# LED-RingCoder.net
KiCad netlist of a schematic drawn in EAGLE
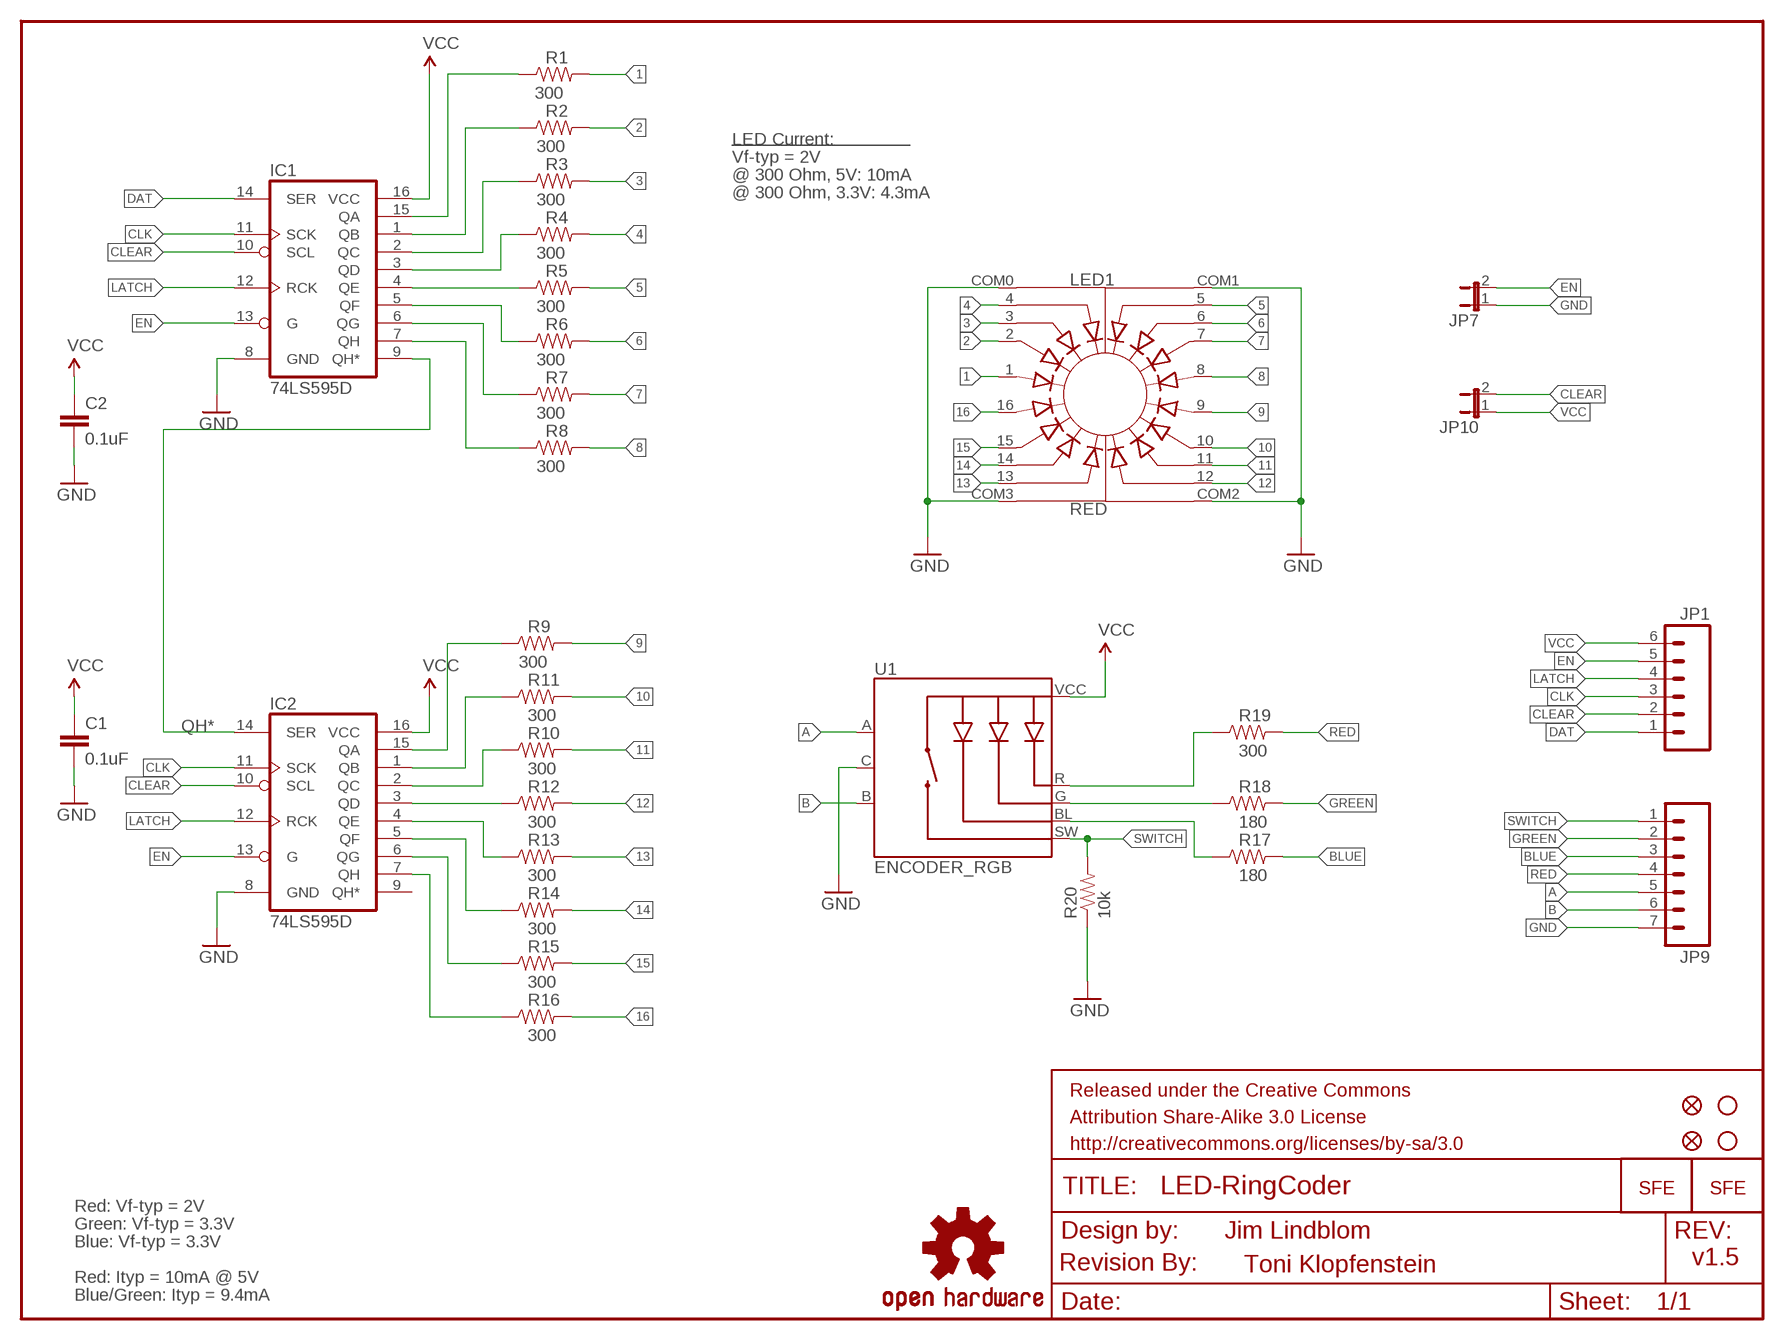
[diagram p0: schematic, sheet 1]

(export (version "E")
  (design (tool "Eeschema 10.0.6"))
  (components
    (comp (ref "C1")
      (value "0.1uF")
      (footprint "eagle-import:0603-CAP")
      (libsource (lib "eagle-import") (part "0.1UF-25V(+80/-20%)(0603)"))
    )
    (comp (ref "C2")
      (value "0.1uF")
      (footprint "eagle-import:0603-CAP")
      (libsource (lib "eagle-import") (part "0.1UF-25V(+80/-20%)(0603)"))
    )
    (comp (ref "FRAME1")
      (value "FRAME-LETTER")
      (footprint "eagle-import:CREATIVE_COMMONS")
      (libsource (lib "eagle-import") (part "FRAME-LETTER"))
    )
    (comp (ref "IC1")
      (value "74LS595D")
      (footprint "eagle-import:SO16")
      (libsource (lib "eagle-import") (part "74595DLS"))
    )
    (comp (ref "IC2")
      (value "74LS595D")
      (footprint "eagle-import:SO16")
      (libsource (lib "eagle-import") (part "74595DLS"))
    )
    (comp (ref "JP1")
      (value "M06SIP")
      (footprint "eagle-import:1X06")
      (libsource (lib "eagle-import") (part "M06SIP"))
    )
    (comp (ref "JP2")
      (value "LOGO-SFENW2")
      (footprint "eagle-import:SFE-NEW-WEB")
      (libsource (lib "eagle-import") (part "LOGO-SFENW2"))
    )
    (comp (ref "JP3")
      (value "STAND-OFF")
      (footprint "eagle-import:STAND-OFF")
      (libsource (lib "eagle-import") (part "STAND-OFF"))
    )
    (comp (ref "JP4")
      (value "STAND-OFF")
      (footprint "eagle-import:STAND-OFF")
      (libsource (lib "eagle-import") (part "STAND-OFF"))
    )
    (comp (ref "JP5")
      (value "FIDUCIAL1X2.5")
      (footprint "eagle-import:FIDUCIAL-1X2.5")
      (libsource (lib "eagle-import") (part "FIDUCIAL1X2.5"))
    )
    (comp (ref "JP6")
      (value "LOGO-SFESK")
      (footprint "eagle-import:SFE-LOGO-FLAME")
      (libsource (lib "eagle-import") (part "LOGO-SFESK"))
    )
    (comp (ref "JP7")
      (value "JUMPER-2SMD-NC")
      (footprint "eagle-import:SJ_2S")
      (libsource (lib "eagle-import") (part "JUMPER-2SMD-NC"))
    )
    (comp (ref "JP8")
      (value "FIDUCIAL1X2.5")
      (footprint "eagle-import:FIDUCIAL-1X2.5")
      (libsource (lib "eagle-import") (part "FIDUCIAL1X2.5"))
    )
    (comp (ref "JP9")
      (value "M07")
      (footprint "eagle-import:1X07")
      (libsource (lib "eagle-import") (part "M07"))
    )
    (comp (ref "JP10")
      (value "JUMPER-2SMD-NC")
      (footprint "eagle-import:SJ_2S")
      (libsource (lib "eagle-import") (part "JUMPER-2SMD-NC"))
    )
    (comp (ref "LED1")
      (value "RED")
      (footprint "eagle-import:LED_RING")
      (libsource (lib "eagle-import") (part "LED_RING"))
    )
    (comp (ref "R1")
      (value "300")
      (footprint "eagle-import:0603-RES")
      (libsource (lib "eagle-import") (part "300OHM-1/10W-1%(0603)"))
    )
    (comp (ref "R2")
      (value "300")
      (footprint "eagle-import:0603-RES")
      (libsource (lib "eagle-import") (part "300OHM-1/10W-1%(0603)"))
    )
    (comp (ref "R3")
      (value "300")
      (footprint "eagle-import:0603-RES")
      (libsource (lib "eagle-import") (part "300OHM-1/10W-1%(0603)"))
    )
    (comp (ref "R4")
      (value "300")
      (footprint "eagle-import:0603-RES")
      (libsource (lib "eagle-import") (part "300OHM-1/10W-1%(0603)"))
    )
    (comp (ref "R5")
      (value "300")
      (footprint "eagle-import:0603-RES")
      (libsource (lib "eagle-import") (part "300OHM-1/10W-1%(0603)"))
    )
    (comp (ref "R6")
      (value "300")
      (footprint "eagle-import:0603-RES")
      (libsource (lib "eagle-import") (part "300OHM-1/10W-1%(0603)"))
    )
    (comp (ref "R7")
      (value "300")
      (footprint "eagle-import:0603-RES")
      (libsource (lib "eagle-import") (part "300OHM-1/10W-1%(0603)"))
    )
    (comp (ref "R8")
      (value "300")
      (footprint "eagle-import:0603-RES")
      (libsource (lib "eagle-import") (part "300OHM-1/10W-1%(0603)"))
    )
    (comp (ref "R9")
      (value "300")
      (footprint "eagle-import:0603-RES")
      (libsource (lib "eagle-import") (part "300OHM-1/10W-1%(0603)"))
    )
    (comp (ref "R10")
      (value "300")
      (footprint "eagle-import:0603-RES")
      (libsource (lib "eagle-import") (part "300OHM-1/10W-1%(0603)"))
    )
    (comp (ref "R11")
      (value "300")
      (footprint "eagle-import:0603-RES")
      (libsource (lib "eagle-import") (part "300OHM-1/10W-1%(0603)"))
    )
    (comp (ref "R12")
      (value "300")
      (footprint "eagle-import:0603-RES")
      (libsource (lib "eagle-import") (part "300OHM-1/10W-1%(0603)"))
    )
    (comp (ref "R13")
      (value "300")
      (footprint "eagle-import:0603-RES")
      (libsource (lib "eagle-import") (part "300OHM-1/10W-1%(0603)"))
    )
    (comp (ref "R14")
      (value "300")
      (footprint "eagle-import:0603-RES")
      (libsource (lib "eagle-import") (part "300OHM-1/10W-1%(0603)"))
    )
    (comp (ref "R15")
      (value "300")
      (footprint "eagle-import:0603-RES")
      (libsource (lib "eagle-import") (part "300OHM-1/10W-1%(0603)"))
    )
    (comp (ref "R16")
      (value "300")
      (footprint "eagle-import:0603-RES")
      (libsource (lib "eagle-import") (part "300OHM-1/10W-1%(0603)"))
    )
    (comp (ref "R17")
      (value "180")
      (footprint "eagle-import:0603-RES")
      (libsource (lib "eagle-import") (part "180OHM1/10W1%(0603)"))
    )
    (comp (ref "R18")
      (value "180")
      (footprint "eagle-import:0603-RES")
      (libsource (lib "eagle-import") (part "180OHM1/10W1%(0603)"))
    )
    (comp (ref "R19")
      (value "300")
      (footprint "eagle-import:0603-RES")
      (libsource (lib "eagle-import") (part "300OHM-1/10W-1%(0603)"))
    )
    (comp (ref "R20")
      (value "10k")
      (footprint "eagle-import:0603-RES")
      (libsource (lib "eagle-import") (part "10KOHM1/10W1%(0603)0603"))
    )
    (comp (ref "U$1")
      (value "REVISION")
      (footprint "eagle-import:REVISION")
      (libsource (lib "eagle-import") (part "REVISION"))
    )
    (comp (ref "U$2")
      (value "OSHW-LOGOS")
      (footprint "eagle-import:OSHW-LOGO-S")
      (libsource (lib "eagle-import") (part "OSHW-LOGOS"))
    )
    (comp (ref "U1")
      (value "ENCODER_RGB")
      (footprint "eagle-import:ENCODER_LED_RGB")
      (libsource (lib "eagle-import") (part "ENCODER_RGB"))
    )
  )
  (nets
    (net (code "1") (name "/QH*") (class "Default")
      (node (ref "IC1") (pin "9") (pinfunction "QH*_9") (pintype "tri_state"))
      (node (ref "IC2") (pin "14") (pinfunction "SER_14") (pintype "input"))
    )
    (net (code "2") (name "1") (class "Default")
      (node (ref "LED1") (pin "1") (pinfunction "1_1") (pintype "passive"))
      (node (ref "R1") (pin "2") (pinfunction "2_2") (pintype "passive"))
    )
    (net (code "3") (name "2") (class "Default")
      (node (ref "LED1") (pin "2") (pinfunction "2_2") (pintype "passive"))
      (node (ref "R2") (pin "2") (pinfunction "2_2") (pintype "passive"))
    )
    (net (code "4") (name "3") (class "Default")
      (node (ref "LED1") (pin "3") (pinfunction "3_3") (pintype "passive"))
      (node (ref "R3") (pin "2") (pinfunction "2_2") (pintype "passive"))
    )
    (net (code "5") (name "4") (class "Default")
      (node (ref "LED1") (pin "4") (pinfunction "4_4") (pintype "passive"))
      (node (ref "R4") (pin "2") (pinfunction "2_2") (pintype "passive"))
    )
    (net (code "6") (name "5") (class "Default")
      (node (ref "LED1") (pin "5") (pinfunction "5_5") (pintype "passive"))
      (node (ref "R5") (pin "2") (pinfunction "2_2") (pintype "passive"))
    )
    (net (code "7") (name "6") (class "Default")
      (node (ref "LED1") (pin "6") (pinfunction "6_6") (pintype "passive"))
      (node (ref "R6") (pin "2") (pinfunction "2_2") (pintype "passive"))
    )
    (net (code "8") (name "7") (class "Default")
      (node (ref "LED1") (pin "7") (pinfunction "7_7") (pintype "passive"))
      (node (ref "R7") (pin "2") (pinfunction "2_2") (pintype "passive"))
    )
    (net (code "9") (name "8") (class "Default")
      (node (ref "LED1") (pin "8") (pinfunction "8_8") (pintype "passive"))
      (node (ref "R8") (pin "2") (pinfunction "2_2") (pintype "passive"))
    )
    (net (code "10") (name "9") (class "Default")
      (node (ref "LED1") (pin "9") (pinfunction "9_9") (pintype "passive"))
      (node (ref "R9") (pin "2") (pinfunction "2_2") (pintype "passive"))
    )
    (net (code "11") (name "10") (class "Default")
      (node (ref "LED1") (pin "10") (pinfunction "10_10") (pintype "passive"))
      (node (ref "R11") (pin "2") (pinfunction "2_2") (pintype "passive"))
    )
    (net (code "12") (name "11") (class "Default")
      (node (ref "LED1") (pin "11") (pinfunction "11_11") (pintype "passive"))
      (node (ref "R10") (pin "2") (pinfunction "2_2") (pintype "passive"))
    )
    (net (code "13") (name "12") (class "Default")
      (node (ref "LED1") (pin "12") (pinfunction "12_12") (pintype "passive"))
      (node (ref "R12") (pin "2") (pinfunction "2_2") (pintype "passive"))
    )
    (net (code "14") (name "13") (class "Default")
      (node (ref "LED1") (pin "13") (pinfunction "13_13") (pintype "passive"))
      (node (ref "R13") (pin "2") (pinfunction "2_2") (pintype "passive"))
    )
    (net (code "15") (name "14") (class "Default")
      (node (ref "LED1") (pin "14") (pinfunction "14_14") (pintype "passive"))
      (node (ref "R14") (pin "2") (pinfunction "2_2") (pintype "passive"))
    )
    (net (code "16") (name "15") (class "Default")
      (node (ref "LED1") (pin "15") (pinfunction "15_15") (pintype "passive"))
      (node (ref "R15") (pin "2") (pinfunction "2_2") (pintype "passive"))
    )
    (net (code "17") (name "16") (class "Default")
      (node (ref "LED1") (pin "16") (pinfunction "16_16") (pintype "passive"))
      (node (ref "R16") (pin "2") (pinfunction "2_2") (pintype "passive"))
    )
    (net (code "18") (name "A") (class "Default")
      (node (ref "JP9") (pin "5") (pinfunction "5_5") (pintype "passive"))
      (node (ref "U1") (pin "A") (pinfunction "A_A") (pintype "bidirectional"))
    )
    (net (code "19") (name "B") (class "Default")
      (node (ref "JP9") (pin "6") (pinfunction "6_6") (pintype "passive"))
      (node (ref "U1") (pin "B") (pinfunction "B_B") (pintype "bidirectional"))
    )
    (net (code "20") (name "BLUE") (class "Default")
      (node (ref "JP9") (pin "3") (pinfunction "3_3") (pintype "passive"))
      (node (ref "R17") (pin "2") (pinfunction "2_2") (pintype "passive"))
    )
    (net (code "21") (name "CLEAR") (class "Default")
      (node (ref "IC1") (pin "10") (pinfunction "SCL_10") (pintype "input"))
      (node (ref "IC2") (pin "10") (pinfunction "SCL_10") (pintype "input"))
      (node (ref "JP1") (pin "2") (pinfunction "2_2") (pintype "passive"))
      (node (ref "JP10") (pin "2") (pinfunction "2_2") (pintype "passive"))
    )
    (net (code "22") (name "CLK") (class "Default")
      (node (ref "IC1") (pin "11") (pinfunction "SCK_11") (pintype "input"))
      (node (ref "IC2") (pin "11") (pinfunction "SCK_11") (pintype "input"))
      (node (ref "JP1") (pin "3") (pinfunction "3_3") (pintype "passive"))
    )
    (net (code "23") (name "DAT") (class "Default")
      (node (ref "IC1") (pin "14") (pinfunction "SER_14") (pintype "input"))
      (node (ref "JP1") (pin "1") (pinfunction "1_1") (pintype "passive"))
    )
    (net (code "24") (name "EN") (class "Default")
      (node (ref "IC1") (pin "13") (pinfunction "G_13") (pintype "input"))
      (node (ref "IC2") (pin "13") (pinfunction "G_13") (pintype "input"))
      (node (ref "JP1") (pin "5") (pinfunction "5_5") (pintype "passive"))
      (node (ref "JP7") (pin "2") (pinfunction "2_2") (pintype "passive"))
    )
    (net (code "25") (name "GND") (class "Default")
      (node (ref "C1") (pin "2") (pinfunction "2_2") (pintype "passive"))
      (node (ref "C2") (pin "2") (pinfunction "2_2") (pintype "passive"))
      (node (ref "IC1") (pin "8") (pinfunction "GND_8") (pintype "power_in"))
      (node (ref "IC2") (pin "8") (pinfunction "GND_8") (pintype "power_in"))
      (node (ref "JP7") (pin "1") (pinfunction "1_1") (pintype "passive"))
      (node (ref "JP9") (pin "7") (pinfunction "7_7") (pintype "passive"))
      (node (ref "LED1") (pin "COM0") (pinfunction "COM0_COM0") (pintype "passive"))
      (node (ref "LED1") (pin "COM1") (pinfunction "COM1_COM1") (pintype "passive"))
      (node (ref "LED1") (pin "COM2") (pinfunction "COM2_COM2") (pintype "passive"))
      (node (ref "LED1") (pin "COM3") (pinfunction "COM3_COM3") (pintype "passive"))
      (node (ref "R20") (pin "1") (pinfunction "1_1") (pintype "passive"))
      (node (ref "U1") (pin "C") (pinfunction "C_C") (pintype "bidirectional"))
    )
    (net (code "26") (name "GREEN") (class "Default")
      (node (ref "JP9") (pin "2") (pinfunction "2_2") (pintype "passive"))
      (node (ref "R18") (pin "2") (pinfunction "2_2") (pintype "passive"))
    )
    (net (code "27") (name "LATCH") (class "Default")
      (node (ref "IC1") (pin "12") (pinfunction "RCK_12") (pintype "input"))
      (node (ref "IC2") (pin "12") (pinfunction "RCK_12") (pintype "input"))
      (node (ref "JP1") (pin "4") (pinfunction "4_4") (pintype "passive"))
    )
    (net (code "28") (name "Net-(IC1-QA)") (class "Default")
      (node (ref "IC1") (pin "15") (pinfunction "QA_15") (pintype "tri_state"))
      (node (ref "R1") (pin "1") (pinfunction "1_1") (pintype "passive"))
    )
    (net (code "29") (name "Net-(IC1-QB)") (class "Default")
      (node (ref "IC1") (pin "1") (pinfunction "QB_1") (pintype "tri_state"))
      (node (ref "R2") (pin "1") (pinfunction "1_1") (pintype "passive"))
    )
    (net (code "30") (name "Net-(IC1-QC)") (class "Default")
      (node (ref "IC1") (pin "2") (pinfunction "QC_2") (pintype "tri_state"))
      (node (ref "R3") (pin "1") (pinfunction "1_1") (pintype "passive"))
    )
    (net (code "31") (name "Net-(IC1-QD)") (class "Default")
      (node (ref "IC1") (pin "3") (pinfunction "QD_3") (pintype "tri_state"))
      (node (ref "R4") (pin "1") (pinfunction "1_1") (pintype "passive"))
    )
    (net (code "32") (name "Net-(IC1-QE)") (class "Default")
      (node (ref "IC1") (pin "4") (pinfunction "QE_4") (pintype "tri_state"))
      (node (ref "R5") (pin "1") (pinfunction "1_1") (pintype "passive"))
    )
    (net (code "33") (name "Net-(IC1-QF)") (class "Default")
      (node (ref "IC1") (pin "5") (pinfunction "QF_5") (pintype "tri_state"))
      (node (ref "R6") (pin "1") (pinfunction "1_1") (pintype "passive"))
    )
    (net (code "34") (name "Net-(IC1-QG)") (class "Default")
      (node (ref "IC1") (pin "6") (pinfunction "QG_6") (pintype "tri_state"))
      (node (ref "R7") (pin "1") (pinfunction "1_1") (pintype "passive"))
    )
    (net (code "35") (name "Net-(IC1-QH)") (class "Default")
      (node (ref "IC1") (pin "7") (pinfunction "QH_7") (pintype "tri_state"))
      (node (ref "R8") (pin "1") (pinfunction "1_1") (pintype "passive"))
    )
    (net (code "36") (name "Net-(IC2-QA)") (class "Default")
      (node (ref "IC2") (pin "15") (pinfunction "QA_15") (pintype "tri_state"))
      (node (ref "R9") (pin "1") (pinfunction "1_1") (pintype "passive"))
    )
    (net (code "37") (name "Net-(IC2-QB)") (class "Default")
      (node (ref "IC2") (pin "1") (pinfunction "QB_1") (pintype "tri_state"))
      (node (ref "R11") (pin "1") (pinfunction "1_1") (pintype "passive"))
    )
    (net (code "38") (name "Net-(IC2-QC)") (class "Default")
      (node (ref "IC2") (pin "2") (pinfunction "QC_2") (pintype "tri_state"))
      (node (ref "R10") (pin "1") (pinfunction "1_1") (pintype "passive"))
    )
    (net (code "39") (name "Net-(IC2-QD)") (class "Default")
      (node (ref "IC2") (pin "3") (pinfunction "QD_3") (pintype "tri_state"))
      (node (ref "R12") (pin "1") (pinfunction "1_1") (pintype "passive"))
    )
    (net (code "40") (name "Net-(IC2-QE)") (class "Default")
      (node (ref "IC2") (pin "4") (pinfunction "QE_4") (pintype "tri_state"))
      (node (ref "R13") (pin "1") (pinfunction "1_1") (pintype "passive"))
    )
    (net (code "41") (name "Net-(IC2-QF)") (class "Default")
      (node (ref "IC2") (pin "5") (pinfunction "QF_5") (pintype "tri_state"))
      (node (ref "R14") (pin "1") (pinfunction "1_1") (pintype "passive"))
    )
    (net (code "42") (name "Net-(IC2-QG)") (class "Default")
      (node (ref "IC2") (pin "6") (pinfunction "QG_6") (pintype "tri_state"))
      (node (ref "R15") (pin "1") (pinfunction "1_1") (pintype "passive"))
    )
    (net (code "43") (name "Net-(IC2-QH)") (class "Default")
      (node (ref "IC2") (pin "7") (pinfunction "QH_7") (pintype "tri_state"))
      (node (ref "R16") (pin "1") (pinfunction "1_1") (pintype "passive"))
    )
    (net (code "44") (name "Net-(R17-Pad1)") (class "Default")
      (node (ref "R17") (pin "1") (pinfunction "1_1") (pintype "passive"))
      (node (ref "U1") (pin "BL") (pinfunction "BL_BL") (pintype "passive"))
    )
    (net (code "45") (name "Net-(R18-Pad1)") (class "Default")
      (node (ref "R18") (pin "1") (pinfunction "1_1") (pintype "passive"))
      (node (ref "U1") (pin "G") (pinfunction "G_G") (pintype "passive"))
    )
    (net (code "46") (name "Net-(R19-Pad1)") (class "Default")
      (node (ref "R19") (pin "1") (pinfunction "1_1") (pintype "passive"))
      (node (ref "U1") (pin "R") (pinfunction "R_R") (pintype "passive"))
    )
    (net (code "47") (name "RED") (class "Default")
      (node (ref "JP9") (pin "4") (pinfunction "4_4") (pintype "passive"))
      (node (ref "R19") (pin "2") (pinfunction "2_2") (pintype "passive"))
    )
    (net (code "48") (name "SWITCH") (class "Default")
      (node (ref "JP9") (pin "1") (pinfunction "1_1") (pintype "passive"))
      (node (ref "R20") (pin "2") (pinfunction "2_2") (pintype "passive"))
      (node (ref "U1") (pin "SW") (pinfunction "SW_SW") (pintype "passive"))
    )
    (net (code "49") (name "VCC") (class "Default")
      (node (ref "C1") (pin "1") (pinfunction "1_1") (pintype "passive"))
      (node (ref "C2") (pin "1") (pinfunction "1_1") (pintype "passive"))
      (node (ref "IC1") (pin "16") (pinfunction "VCC_16") (pintype "power_in"))
      (node (ref "IC2") (pin "16") (pinfunction "VCC_16") (pintype "power_in"))
      (node (ref "JP1") (pin "6") (pinfunction "6_6") (pintype "passive"))
      (node (ref "JP10") (pin "1") (pinfunction "1_1") (pintype "passive"))
      (node (ref "U1") (pin "VCC") (pinfunction "VCC_VCC") (pintype "passive"))
    )
    (net (code "50") (name "unconnected-(IC2-QH*-Pad9)") (class "Default")
      (node (ref "IC2") (pin "9") (pinfunction "QH*_9") (pintype "tri_state"))
    )
  )
)
